# pendrive.net
KiCad netlist of a schematic drawn in EAGLE
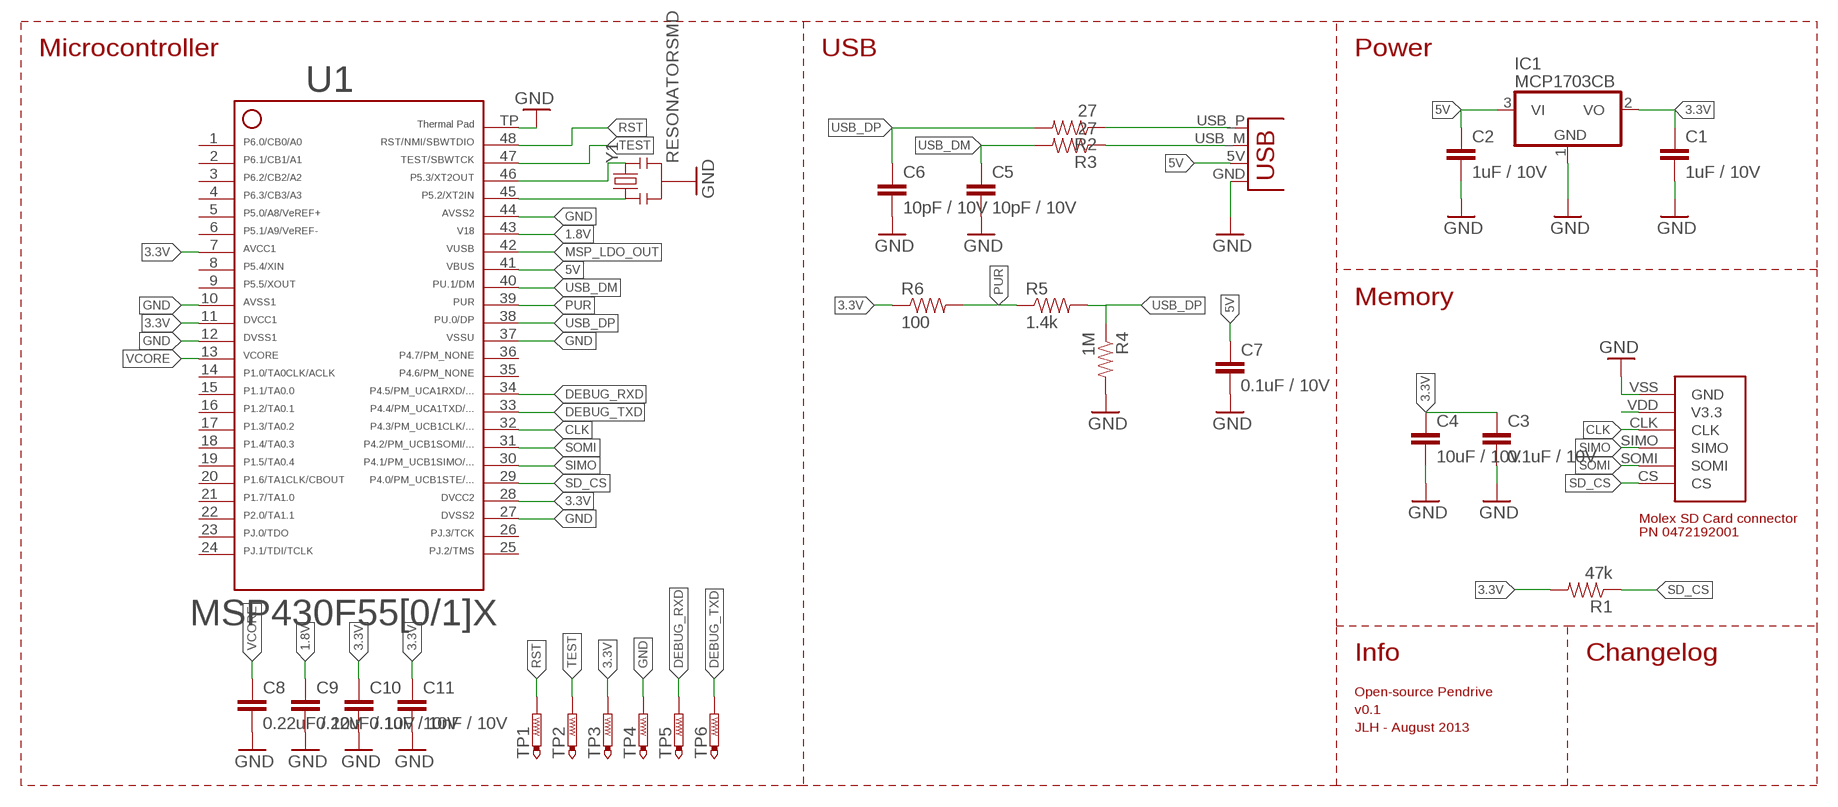
[diagram p0: schematic, sheet 1]

(export (version "E")
  (design (tool "Eeschema 10.0.6"))
  (components
    (comp (ref "C1")
      (value "1uF / 10V")
      (footprint "eagle-import:0402-CAP")
      (libsource (lib "eagle-import") (part "CAP0402-CAP"))
    )
    (comp (ref "C2")
      (value "1uF / 10V")
      (footprint "eagle-import:0402-CAP")
      (libsource (lib "eagle-import") (part "CAP0402-CAP"))
    )
    (comp (ref "C3")
      (value "0.1uF / 10V")
      (footprint "eagle-import:0402-CAP")
      (libsource (lib "eagle-import") (part "CAP0402-CAP"))
    )
    (comp (ref "C4")
      (value "10uF / 10V")
      (footprint "eagle-import:1206")
      (libsource (lib "eagle-import") (part "CAP1206"))
    )
    (comp (ref "C5")
      (value "10pF / 10V")
      (footprint "eagle-import:0402-CAP")
      (libsource (lib "eagle-import") (part "CAP0402-CAP"))
    )
    (comp (ref "C6")
      (value "10pF / 10V")
      (footprint "eagle-import:0402-CAP")
      (libsource (lib "eagle-import") (part "CAP0402-CAP"))
    )
    (comp (ref "C7")
      (value "0.1uF / 10V")
      (footprint "eagle-import:0402-CAP")
      (libsource (lib "eagle-import") (part "CAP0402-CAP"))
    )
    (comp (ref "C8")
      (value "0.22uF / 10V")
      (footprint "eagle-import:0402-CAP")
      (libsource (lib "eagle-import") (part "CAP0402-CAP"))
    )
    (comp (ref "C9")
      (value "0.22uF / 10V")
      (footprint "eagle-import:0402-CAP")
      (libsource (lib "eagle-import") (part "CAP0402-CAP"))
    )
    (comp (ref "C10")
      (value "0.1uF / 10V")
      (footprint "eagle-import:0402-CAP")
      (libsource (lib "eagle-import") (part "CAP0402-CAP"))
    )
    (comp (ref "C11")
      (value "10nF / 10V")
      (footprint "eagle-import:0402-CAP")
      (libsource (lib "eagle-import") (part "CAP0402-CAP"))
    )
    (comp (ref "IC1")
      (value "MCP1703CB")
      (footprint "eagle-import:SOT23")
      (libsource (lib "eagle-import") (part "MCP1703CB"))
    )
    (comp (ref "R1")
      (value "47k")
      (footprint "eagle-import:0402-RES")
      (libsource (lib "eagle-import") (part "RESISTOR0402-RES"))
    )
    (comp (ref "R2")
      (value "27")
      (footprint "eagle-import:0402-RES")
      (libsource (lib "eagle-import") (part "RESISTOR0402-RES"))
    )
    (comp (ref "R3")
      (value "27")
      (footprint "eagle-import:0402-RES")
      (libsource (lib "eagle-import") (part "RESISTOR0402-RES"))
    )
    (comp (ref "R4")
      (value "1M")
      (footprint "eagle-import:0402-RES")
      (libsource (lib "eagle-import") (part "RESISTOR0402-RES"))
    )
    (comp (ref "R5")
      (value "1.4k")
      (footprint "eagle-import:0402-RES")
      (libsource (lib "eagle-import") (part "RESISTOR0402-RES"))
    )
    (comp (ref "R6")
      (value "100")
      (footprint "eagle-import:0402-RES")
      (libsource (lib "eagle-import") (part "RESISTOR0402-RES"))
    )
    (comp (ref "TP1")
      (value "PTR1TP10SQ")
      (footprint "eagle-import:TP10SQ")
      (libsource (lib "eagle-import") (part "PTR1TP10SQ"))
    )
    (comp (ref "TP2")
      (value "PTR1TP10SQ")
      (footprint "eagle-import:TP10SQ")
      (libsource (lib "eagle-import") (part "PTR1TP10SQ"))
    )
    (comp (ref "TP3")
      (value "PTR1TP10SQ")
      (footprint "eagle-import:TP10SQ")
      (libsource (lib "eagle-import") (part "PTR1TP10SQ"))
    )
    (comp (ref "TP4")
      (value "PTR1TP10SQ")
      (footprint "eagle-import:TP10SQ")
      (libsource (lib "eagle-import") (part "PTR1TP10SQ"))
    )
    (comp (ref "TP5")
      (value "PTR1TP10SQ")
      (footprint "eagle-import:TP10SQ")
      (libsource (lib "eagle-import") (part "PTR1TP10SQ"))
    )
    (comp (ref "TP6")
      (value "PTR1TP10SQ")
      (footprint "eagle-import:TP10SQ")
      (libsource (lib "eagle-import") (part "PTR1TP10SQ"))
    )
    (comp (ref "U1")
      (value "F55[0/1]X---RGZ48")
      (footprint "eagle-import:RGZ48")
      (libsource (lib "eagle-import") (part "F55[0/1]X---RGZ48"))
    )
    (comp (ref "U2")
      (value "MICROSD-MOLEX")
      (footprint "eagle-import:MICROSD-MOLEX")
      (libsource (lib "eagle-import") (part "MICROSD-MOLEX"))
    )
    (comp (ref "X1")
      (value "USBPCB")
      (footprint "eagle-import:USB-A-PCB")
      (libsource (lib "eagle-import") (part "USBPCB"))
    )
    (comp (ref "Y1")
      (value "RESONATORSMD")
      (footprint "eagle-import:RESONATOR-SMD")
      (libsource (lib "eagle-import") (part "RESONATORSMD"))
    )
  )
  (nets
    (net (code "1") (name "1.8V") (class "Default")
      (node (ref "C9") (pin "1") (pinfunction "1_1") (pintype "passive"))
      (node (ref "U1") (pin "43") (pinfunction "43_43") (pintype "power_in"))
    )
    (net (code "2") (name "3.3V") (class "Default")
      (node (ref "C1") (pin "1") (pinfunction "1_1") (pintype "passive"))
      (node (ref "C10") (pin "1") (pinfunction "1_1") (pintype "passive"))
      (node (ref "C11") (pin "1") (pinfunction "1_1") (pintype "passive"))
      (node (ref "C3") (pin "1") (pinfunction "1_1") (pintype "passive"))
      (node (ref "C4") (pin "1") (pinfunction "1_1") (pintype "passive"))
      (node (ref "IC1") (pin "2") (pinfunction "VO_2") (pintype "passive"))
      (node (ref "R1") (pin "2") (pinfunction "2_2") (pintype "passive"))
      (node (ref "R6") (pin "1") (pinfunction "1_1") (pintype "passive"))
      (node (ref "TP3") (pin "TP") (pinfunction "TP_TP") (pintype "input"))
      (node (ref "U1") (pin "11") (pinfunction "11_11") (pintype "power_in"))
      (node (ref "U1") (pin "28") (pinfunction "28_28") (pintype "power_in"))
      (node (ref "U1") (pin "7") (pinfunction "7_7") (pintype "power_in"))
      (node (ref "U2") (pin "VDD") (pinfunction "V3.3_VDD") (pintype "bidirectional"))
    )
    (net (code "3") (name "5V") (class "Default")
      (node (ref "C2") (pin "1") (pinfunction "1_1") (pintype "passive"))
      (node (ref "C7") (pin "1") (pinfunction "1_1") (pintype "passive"))
      (node (ref "IC1") (pin "3") (pinfunction "VI_3") (pintype "input"))
      (node (ref "U1") (pin "41") (pinfunction "41_41") (pintype "power_in"))
      (node (ref "X1") (pin "5V") (pinfunction "VBUS_5V") (pintype "bidirectional"))
    )
    (net (code "4") (name "CLK") (class "Default")
      (node (ref "U1") (pin "32") (pinfunction "32_32") (pintype "bidirectional"))
      (node (ref "U2") (pin "CLK") (pinfunction "CLK_CLK") (pintype "bidirectional"))
    )
    (net (code "5") (name "DEBUG_RXD") (class "Default")
      (node (ref "TP5") (pin "TP") (pinfunction "TP_TP") (pintype "input"))
      (node (ref "U1") (pin "34") (pinfunction "34_34") (pintype "bidirectional"))
    )
    (net (code "6") (name "DEBUG_TXD") (class "Default")
      (node (ref "TP6") (pin "TP") (pinfunction "TP_TP") (pintype "input"))
      (node (ref "U1") (pin "33") (pinfunction "33_33") (pintype "bidirectional"))
    )
    (net (code "7") (name "GND") (class "Default")
      (node (ref "C1") (pin "2") (pinfunction "2_2") (pintype "passive"))
      (node (ref "C10") (pin "2") (pinfunction "2_2") (pintype "passive"))
      (node (ref "C11") (pin "2") (pinfunction "2_2") (pintype "passive"))
      (node (ref "C2") (pin "2") (pinfunction "2_2") (pintype "passive"))
      (node (ref "C3") (pin "2") (pinfunction "2_2") (pintype "passive"))
      (node (ref "C4") (pin "2") (pinfunction "2_2") (pintype "passive"))
      (node (ref "C5") (pin "2") (pinfunction "2_2") (pintype "passive"))
      (node (ref "C6") (pin "2") (pinfunction "2_2") (pintype "passive"))
      (node (ref "C7") (pin "2") (pinfunction "2_2") (pintype "passive"))
      (node (ref "C8") (pin "2") (pinfunction "2_2") (pintype "passive"))
      (node (ref "C9") (pin "2") (pinfunction "2_2") (pintype "passive"))
      (node (ref "IC1") (pin "1") (pinfunction "GND_1") (pintype "passive"))
      (node (ref "R4") (pin "2") (pinfunction "2_2") (pintype "passive"))
      (node (ref "TP4") (pin "TP") (pinfunction "TP_TP") (pintype "input"))
      (node (ref "U1") (pin "10") (pinfunction "10_10") (pintype "power_in"))
      (node (ref "U1") (pin "12") (pinfunction "12_12") (pintype "power_in"))
      (node (ref "U1") (pin "27") (pinfunction "27_27") (pintype "power_in"))
      (node (ref "U1") (pin "37") (pinfunction "37_37") (pintype "power_in"))
      (node (ref "U1") (pin "44") (pinfunction "44_44") (pintype "power_in"))
      (node (ref "U1") (pin "TP") (pinfunction "49_TP") (pintype "power_in"))
      (node (ref "U2") (pin "VSS") (pinfunction "GND_VSS") (pintype "bidirectional"))
      (node (ref "X1") (pin "GND") (pinfunction "GND_GND") (pintype "bidirectional"))
      (node (ref "Y1") (pin "2") (pinfunction "2_2") (pintype "passive"))
    )
    (net (code "8") (name "MSP_LDO_OUT") (class "Default")
      (node (ref "U1") (pin "42") (pinfunction "42_42") (pintype "power_in"))
    )
    (net (code "9") (name "Net-(U1-Pad45)") (class "Default")
      (node (ref "U1") (pin "45") (pinfunction "45_45") (pintype "bidirectional"))
      (node (ref "Y1") (pin "1") (pinfunction "1_1") (pintype "passive"))
    )
    (net (code "10") (name "Net-(U1-Pad46)") (class "Default")
      (node (ref "U1") (pin "46") (pinfunction "46_46") (pintype "bidirectional"))
      (node (ref "Y1") (pin "3") (pinfunction "3_3") (pintype "passive"))
    )
    (net (code "11") (name "Net-(X1-D+)") (class "Default")
      (node (ref "R2") (pin "1") (pinfunction "1_1") (pintype "passive"))
      (node (ref "X1") (pin "USB_P") (pinfunction "D+_USB_P") (pintype "bidirectional"))
    )
    (net (code "12") (name "Net-(X1-D-)") (class "Default")
      (node (ref "R3") (pin "1") (pinfunction "1_1") (pintype "passive"))
      (node (ref "X1") (pin "USB_M") (pinfunction "D-_USB_M") (pintype "bidirectional"))
    )
    (net (code "13") (name "PUR") (class "Default")
      (node (ref "R5") (pin "1") (pinfunction "1_1") (pintype "passive"))
      (node (ref "R6") (pin "2") (pinfunction "2_2") (pintype "passive"))
      (node (ref "U1") (pin "39") (pinfunction "39_39") (pintype "bidirectional"))
    )
    (net (code "14") (name "RST") (class "Default")
      (node (ref "TP1") (pin "TP") (pinfunction "TP_TP") (pintype "input"))
      (node (ref "U1") (pin "48") (pinfunction "48_48") (pintype "bidirectional"))
    )
    (net (code "15") (name "SD_CS") (class "Default")
      (node (ref "R1") (pin "1") (pinfunction "1_1") (pintype "passive"))
      (node (ref "U1") (pin "29") (pinfunction "29_29") (pintype "bidirectional"))
      (node (ref "U2") (pin "CS") (pinfunction "CS_CS") (pintype "bidirectional"))
    )
    (net (code "16") (name "SIMO") (class "Default")
      (node (ref "U1") (pin "30") (pinfunction "30_30") (pintype "bidirectional"))
      (node (ref "U2") (pin "SIMO") (pinfunction "SIMO_SIMO") (pintype "bidirectional"))
    )
    (net (code "17") (name "SOMI") (class "Default")
      (node (ref "U1") (pin "31") (pinfunction "31_31") (pintype "bidirectional"))
      (node (ref "U2") (pin "SOMI") (pinfunction "SOMI_SOMI") (pintype "bidirectional"))
    )
    (net (code "18") (name "TEST") (class "Default")
      (node (ref "TP2") (pin "TP") (pinfunction "TP_TP") (pintype "input"))
      (node (ref "U1") (pin "47") (pinfunction "47_47") (pintype "input"))
    )
    (net (code "19") (name "USB_DM") (class "Default")
      (node (ref "C5") (pin "1") (pinfunction "1_1") (pintype "passive"))
      (node (ref "R3") (pin "2") (pinfunction "2_2") (pintype "passive"))
      (node (ref "U1") (pin "40") (pinfunction "40_40") (pintype "bidirectional"))
    )
    (net (code "20") (name "USB_DP") (class "Default")
      (node (ref "C6") (pin "1") (pinfunction "1_1") (pintype "passive"))
      (node (ref "R2") (pin "2") (pinfunction "2_2") (pintype "passive"))
      (node (ref "R4") (pin "1") (pinfunction "1_1") (pintype "passive"))
      (node (ref "R5") (pin "2") (pinfunction "2_2") (pintype "passive"))
      (node (ref "U1") (pin "38") (pinfunction "38_38") (pintype "bidirectional"))
    )
    (net (code "21") (name "VCORE") (class "Default")
      (node (ref "C8") (pin "1") (pinfunction "1_1") (pintype "passive"))
      (node (ref "U1") (pin "13") (pinfunction "13_13") (pintype "power_in"))
    )
    (net (code "22") (name "unconnected-(U1-Pad1)") (class "Default")
      (node (ref "U1") (pin "1") (pinfunction "1_1") (pintype "bidirectional"))
    )
    (net (code "23") (name "unconnected-(U1-Pad2)") (class "Default")
      (node (ref "U1") (pin "2") (pinfunction "2_2") (pintype "bidirectional"))
    )
    (net (code "24") (name "unconnected-(U1-Pad3)") (class "Default")
      (node (ref "U1") (pin "3") (pinfunction "3_3") (pintype "bidirectional"))
    )
    (net (code "25") (name "unconnected-(U1-Pad4)") (class "Default")
      (node (ref "U1") (pin "4") (pinfunction "4_4") (pintype "input"))
    )
    (net (code "26") (name "unconnected-(U1-Pad5)") (class "Default")
      (node (ref "U1") (pin "5") (pinfunction "5_5") (pintype "bidirectional"))
    )
    (net (code "27") (name "unconnected-(U1-Pad6)") (class "Default")
      (node (ref "U1") (pin "6") (pinfunction "6_6") (pintype "bidirectional"))
    )
    (net (code "28") (name "unconnected-(U1-Pad8)") (class "Default")
      (node (ref "U1") (pin "8") (pinfunction "8_8") (pintype "bidirectional"))
    )
    (net (code "29") (name "unconnected-(U1-Pad9)") (class "Default")
      (node (ref "U1") (pin "9") (pinfunction "9_9") (pintype "bidirectional"))
    )
    (net (code "30") (name "unconnected-(U1-Pad14)") (class "Default")
      (node (ref "U1") (pin "14") (pinfunction "14_14") (pintype "bidirectional"))
    )
    (net (code "31") (name "unconnected-(U1-Pad15)") (class "Default")
      (node (ref "U1") (pin "15") (pinfunction "15_15") (pintype "bidirectional"))
    )
    (net (code "32") (name "unconnected-(U1-Pad16)") (class "Default")
      (node (ref "U1") (pin "16") (pinfunction "16_16") (pintype "bidirectional"))
    )
    (net (code "33") (name "unconnected-(U1-Pad17)") (class "Default")
      (node (ref "U1") (pin "17") (pinfunction "17_17") (pintype "bidirectional"))
    )
    (net (code "34") (name "unconnected-(U1-Pad18)") (class "Default")
      (node (ref "U1") (pin "18") (pinfunction "18_18") (pintype "bidirectional"))
    )
    (net (code "35") (name "unconnected-(U1-Pad19)") (class "Default")
      (node (ref "U1") (pin "19") (pinfunction "19_19") (pintype "bidirectional"))
    )
    (net (code "36") (name "unconnected-(U1-Pad20)") (class "Default")
      (node (ref "U1") (pin "20") (pinfunction "20_20") (pintype "bidirectional"))
    )
    (net (code "37") (name "unconnected-(U1-Pad21)") (class "Default")
      (node (ref "U1") (pin "21") (pinfunction "21_21") (pintype "bidirectional"))
    )
    (net (code "38") (name "unconnected-(U1-Pad22)") (class "Default")
      (node (ref "U1") (pin "22") (pinfunction "22_22") (pintype "bidirectional"))
    )
    (net (code "39") (name "unconnected-(U1-Pad23)") (class "Default")
      (node (ref "U1") (pin "23") (pinfunction "23_23") (pintype "bidirectional"))
    )
    (net (code "40") (name "unconnected-(U1-Pad24)") (class "Default")
      (node (ref "U1") (pin "24") (pinfunction "24_24") (pintype "bidirectional"))
    )
    (net (code "41") (name "unconnected-(U1-Pad25)") (class "Default")
      (node (ref "U1") (pin "25") (pinfunction "25_25") (pintype "bidirectional"))
    )
    (net (code "42") (name "unconnected-(U1-Pad26)") (class "Default")
      (node (ref "U1") (pin "26") (pinfunction "26_26") (pintype "bidirectional"))
    )
    (net (code "43") (name "unconnected-(U1-Pad35)") (class "Default")
      (node (ref "U1") (pin "35") (pinfunction "35_35") (pintype "bidirectional"))
    )
    (net (code "44") (name "unconnected-(U1-Pad36)") (class "Default")
      (node (ref "U1") (pin "36") (pinfunction "36_36") (pintype "bidirectional"))
    )
  )
)
